# MQ6.net
KiCad netlist of a schematic drawn in Altium Designer
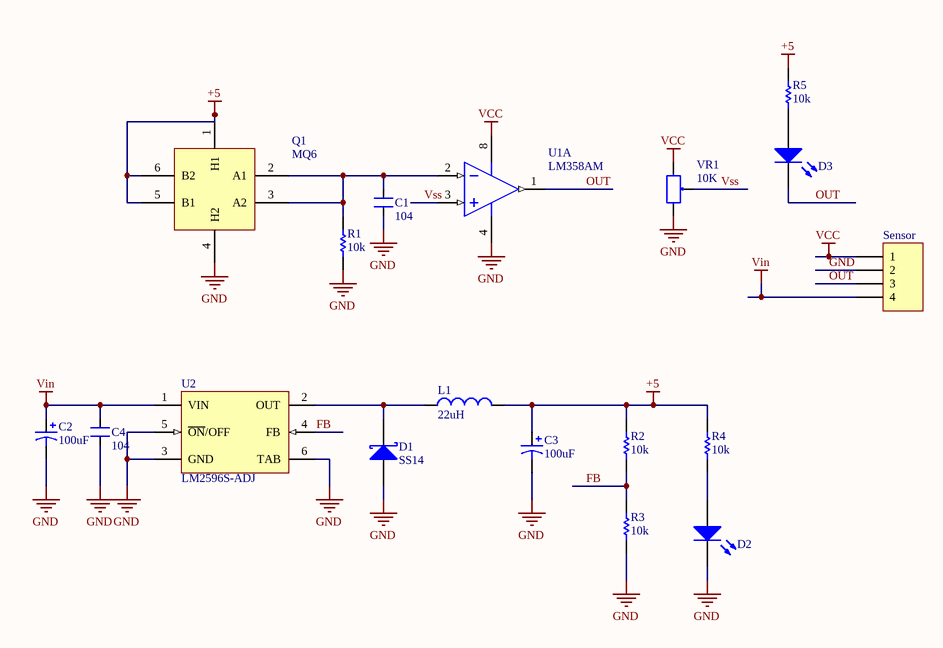
[diagram p0: MQ6.SchDoc]

(export (version "E")
  (design (tool "Eeschema 10.0.6"))
  (components
    (comp (ref "C1")
      (value "104")
      (footprint "SMD 0603")
      (fields (field (name "Comment") "CAP NP"))
      (libsource (lib "Tuan") (part "CAP NP"))
    )
    (comp (ref "C2")
      (value "100uF")
      (footprint "SMD CAP 7x7")
      (fields (field (name "Comment") "Cap"))
      (libsource (lib "Tuan") (part "Cap"))
    )
    (comp (ref "C3")
      (value "100uF")
      (footprint "SMD CAP 7x7")
      (fields (field (name "Comment") "Cap"))
      (libsource (lib "Tuan") (part "Cap"))
    )
    (comp (ref "C4")
      (value "104")
      (footprint "SMD 0603")
      (fields (field (name "Comment") "CAP NP"))
      (libsource (lib "Tuan") (part "CAP NP"))
    )
    (comp (ref "D1") (value "SS14") (footprint "SS14") (libsource (lib "Tuan") (part "Diode Schottky")))
    (comp (ref "D2") (value "Led") (footprint "Led 0805") (libsource (lib "Tuan") (part "Led")))
    (comp (ref "D3") (value "Led") (footprint "Led 0805") (libsource (lib "Tuan") (part "Led")))
    (comp (ref "L1")
      (value "22uH")
      (footprint "Inductor C8x10")
      (fields (field (name "Comment") "Inductor"))
      (libsource (lib "Tuan") (part "Inductor"))
    )
    (comp (ref "Q1") (value "MQ6") (footprint "MQ6") (libsource (lib "Tuan") (part "MQ6")))
    (comp (ref "R1")
      (value "10k")
      (footprint "SMD 0603")
      (fields (field (name "Comment") "Res"))
      (libsource (lib "Tuan") (part "Res"))
    )
    (comp (ref "R2")
      (value "10k")
      (footprint "SMD 0603")
      (fields (field (name "Comment") "Res"))
      (libsource (lib "Tuan") (part "Res"))
    )
    (comp (ref "R3")
      (value "10k")
      (footprint "SMD 0603")
      (fields (field (name "Comment") "Res"))
      (libsource (lib "Tuan") (part "Res"))
    )
    (comp (ref "R4")
      (value "10k")
      (footprint "SMD 0603")
      (fields (field (name "Comment") "Res"))
      (libsource (lib "Tuan") (part "Res"))
    )
    (comp (ref "R5")
      (value "10k")
      (footprint "SMD 0603")
      (fields (field (name "Comment") "Res"))
      (libsource (lib "Tuan") (part "Res"))
    )
    (comp (ref "Sensor")
      (value "Header 4")
      (footprint "HDR1X4")
      (description "Header, 4-Pin")
      (fields (field (name "PUBLISHER") "Altium Limited"))
      (libsource (lib "Miscellaneous Connectors") (part "Header 4"))
    )
    (comp (ref "U1")
      (value "LM358AM")
      (footprint "M08A_N")
      (description "Low Power Dual Operational Amplifier")
      (fields
        (field (name "MANUFACTURER") "National Semiconductor")
        (field (name "DIGIKEYPARTNUMBER") "LM358AMXCT-ND")
        (field (name "PUBLISHER") "Altium Limited")
      )
      (libsource (lib "NSC Amplifier") (part "LM358AM"))
    )
    (comp (ref "U2")
      (value "LM2596S-ADJ")
      (footprint "TS5B_N")
      (description "SIMPLE SWITCHER Power Converter 150 KHz 3A Step-Down Voltage Regulator")
      (fields
        (field (name "MANUFACTURER") "National Semiconductor")
        (field (name "DIGIKEYPARTNUMBER") "LM2596S-ADJ-ND")
        (field (name "PUBLISHER") "Altium Limited")
      )
      (libsource (lib "NSC Switcher") (part "LM2596S-ADJ"))
    )
    (comp (ref "VR1")
      (value "10K")
      (footprint "VR1")
      (description "Var Resistor")
      (libsource (lib "syhaunguyen") (part "VR"))
    )
  )
  (nets
    (net (code "1") (name "+5") (class "Default")
      (node (ref "C3") (pin "1") (pinfunction "1_1") (pintype "passive"))
      (node (ref "L1") (pin "2") (pinfunction "2_2") (pintype "passive"))
      (node (ref "Q1") (pin "1") (pinfunction "H1_1") (pintype "power_in"))
      (node (ref "Q1") (pin "5") (pinfunction "B1_5") (pintype "power_in"))
      (node (ref "Q1") (pin "6") (pinfunction "B2_6") (pintype "power_in"))
      (node (ref "R2") (pin "2") (pinfunction "2_2") (pintype "passive"))
      (node (ref "R4") (pin "2") (pinfunction "2_2") (pintype "passive"))
      (node (ref "R5") (pin "2") (pinfunction "2_2") (pintype "passive"))
    )
    (net (code "2") (name "/FB") (class "Default")
      (node (ref "R2") (pin "1") (pinfunction "1_1") (pintype "passive"))
      (node (ref "R3") (pin "2") (pinfunction "2_2") (pintype "passive"))
      (node (ref "U2") (pin "4") (pinfunction "FB_4") (pintype "input"))
    )
    (net (code "3") (name "/OUT") (class "Default")
      (node (ref "D3") (pin "2") (pinfunction "K_2") (pintype "passive"))
      (node (ref "Sensor") (pin "3") (pinfunction "3_3") (pintype "passive"))
      (node (ref "U1") (pin "1") (pinfunction "OUTA_1") (pintype "output"))
    )
    (net (code "4") (name "/Vss") (class "Default")
      (node (ref "U1") (pin "3") (pinfunction "INA+_3") (pintype "input"))
      (node (ref "VR1") (pin "2") (pinfunction "2_2") (pintype "passive"))
    )
    (net (code "5") (name "GND") (class "Default")
      (node (ref "C1") (pin "1") (pinfunction "1_1") (pintype "passive"))
      (node (ref "C2") (pin "2") (pinfunction "2_2") (pintype "passive"))
      (node (ref "C3") (pin "2") (pinfunction "2_2") (pintype "passive"))
      (node (ref "C4") (pin "1") (pinfunction "1_1") (pintype "passive"))
      (node (ref "D1") (pin "1") (pinfunction "A_1") (pintype "passive"))
      (node (ref "D2") (pin "2") (pinfunction "K_2") (pintype "passive"))
      (node (ref "Q1") (pin "4") (pinfunction "H2_4") (pintype "power_in"))
      (node (ref "R1") (pin "1") (pinfunction "1_1") (pintype "passive"))
      (node (ref "R3") (pin "1") (pinfunction "1_1") (pintype "passive"))
      (node (ref "Sensor") (pin "2") (pinfunction "2_2") (pintype "passive"))
      (node (ref "U1") (pin "4") (pinfunction "GND_4") (pintype "power_in"))
      (node (ref "U2") (pin "3") (pinfunction "GND_3") (pintype "power_in"))
      (node (ref "U2") (pin "5") (pinfunction "~{ON}/OFF_5") (pintype "input"))
      (node (ref "U2") (pin "6") (pinfunction "TAB_6") (pintype "power_in"))
      (node (ref "VR1") (pin "3") (pinfunction "3_3") (pintype "passive"))
    )
    (net (code "6") (name "Net-(D1-K)") (class "Default")
      (node (ref "D1") (pin "2") (pinfunction "K_2") (pintype "passive"))
      (node (ref "L1") (pin "1") (pinfunction "1_1") (pintype "passive"))
      (node (ref "U2") (pin "2") (pinfunction "OUT_2") (pintype "power_in"))
    )
    (net (code "7") (name "Net-(D2-A)") (class "Default")
      (node (ref "D2") (pin "1") (pinfunction "A_1") (pintype "passive"))
      (node (ref "R4") (pin "1") (pinfunction "1_1") (pintype "passive"))
    )
    (net (code "8") (name "Net-(D3-A)") (class "Default")
      (node (ref "D3") (pin "1") (pinfunction "A_1") (pintype "passive"))
      (node (ref "R5") (pin "1") (pinfunction "1_1") (pintype "passive"))
    )
    (net (code "9") (name "Net-(Q1-A1)") (class "Default")
      (node (ref "C1") (pin "2") (pinfunction "2_2") (pintype "passive"))
      (node (ref "Q1") (pin "2") (pinfunction "A1_2") (pintype "power_in"))
      (node (ref "Q1") (pin "3") (pinfunction "A2_3") (pintype "power_in"))
      (node (ref "R1") (pin "2") (pinfunction "2_2") (pintype "passive"))
      (node (ref "U1") (pin "2") (pinfunction "INA-_2") (pintype "input"))
    )
    (net (code "10") (name "VCC") (class "Default")
      (node (ref "Sensor") (pin "1") (pinfunction "1_1") (pintype "passive"))
      (node (ref "U1") (pin "8") (pinfunction "V+_8") (pintype "power_in"))
      (node (ref "VR1") (pin "1") (pinfunction "1_1") (pintype "passive"))
    )
    (net (code "11") (name "Vin") (class "Default")
      (node (ref "C2") (pin "1") (pinfunction "1_1") (pintype "passive"))
      (node (ref "C4") (pin "2") (pinfunction "2_2") (pintype "passive"))
      (node (ref "Sensor") (pin "4") (pinfunction "4_4") (pintype "passive"))
      (node (ref "U2") (pin "1") (pinfunction "VIN_1") (pintype "power_in"))
    )
  )
)
